# EMoC_Page1.net
KiCad netlist of a schematic drawn in Altium Designer
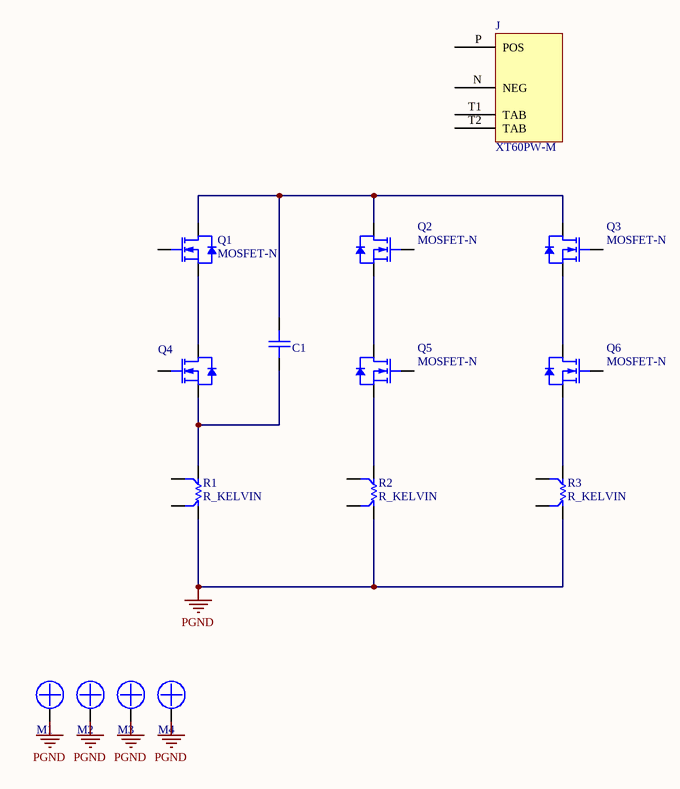
[diagram p0: EMoC_Page1.SchDoc]

(export (version "E")
  (design (tool "Eeschema 10.0.6"))
  (components
    (comp (ref "C1") (value "~") (footprint "C0603N") (libsource (lib "libysk") (part "C")))
    (comp (ref "J")
      (value "XT60PW-M")
      (footprint "XT60PW-M")
      (description "XT60, Male, THT, R/A")
      (libsource (lib "libysk") (part "XT60PW-M"))
    )
    (comp (ref "M1")
      (value "Mounting_Screw")
      (footprint "MOUNT_HOLE_3.2")
      (libsource (lib "libysk") (part "Mounting_Screw"))
    )
    (comp (ref "M2")
      (value "Mounting_Screw")
      (footprint "MOUNT_HOLE_3.2")
      (libsource (lib "libysk") (part "Mounting_Screw"))
    )
    (comp (ref "M3")
      (value "Mounting_Screw")
      (footprint "MOUNT_HOLE_3.2")
      (libsource (lib "libysk") (part "Mounting_Screw"))
    )
    (comp (ref "M4")
      (value "Mounting_Screw")
      (footprint "MOUNT_HOLE_3.2")
      (libsource (lib "libysk") (part "Mounting_Screw"))
    )
    (comp (ref "Q1")
      (value "MOSFET-N")
      (footprint "DFN-5 (SO-8FL)")
      (libsource (lib "libysk") (part "MOSFET-N"))
    )
    (comp (ref "Q2")
      (value "MOSFET-N")
      (footprint "DFN-5 (SO-8FL)")
      (libsource (lib "libysk") (part "MOSFET-N"))
    )
    (comp (ref "Q3")
      (value "MOSFET-N")
      (footprint "DFN-5 (SO-8FL)")
      (libsource (lib "libysk") (part "MOSFET-N"))
    )
    (comp (ref "Q4")
      (value "MOSFET-N")
      (footprint "DFN-5 (SO-8FL)")
      (libsource (lib "libysk") (part "MOSFET-N"))
    )
    (comp (ref "Q5")
      (value "MOSFET-N")
      (footprint "DFN-5 (SO-8FL)")
      (libsource (lib "libysk") (part "MOSFET-N"))
    )
    (comp (ref "Q6")
      (value "MOSFET-N")
      (footprint "DFN-5 (SO-8FL)")
      (libsource (lib "libysk") (part "MOSFET-N"))
    )
    (comp (ref "R1")
      (value "R_KELVIN")
      (footprint "CSS2H-2512N_KELVIN")
      (libsource (lib "libysk") (part "R_KELVIN"))
    )
    (comp (ref "R2")
      (value "R_KELVIN")
      (footprint "CSS2H-2512N_KELVIN")
      (libsource (lib "libysk") (part "R_KELVIN"))
    )
    (comp (ref "R3")
      (value "R_KELVIN")
      (footprint "CSS2H-2512N_KELVIN")
      (libsource (lib "libysk") (part "R_KELVIN"))
    )
  )
  (nets
    (net (code "1") (name "Net-(C1-Pad1)") (class "Default")
      (node (ref "C1") (pin "1") (pinfunction "1_1") (pintype "passive"))
      (node (ref "Q4") (pin "S") (pinfunction "S_S") (pintype "passive"))
      (node (ref "R1") (pin "2") (pinfunction "2_2") (pintype "passive"))
    )
    (net (code "2") (name "Net-(C1-Pad2)") (class "Default")
      (node (ref "C1") (pin "2") (pinfunction "2_2") (pintype "passive"))
      (node (ref "Q1") (pin "D") (pinfunction "D_D") (pintype "passive"))
      (node (ref "Q2") (pin "D") (pinfunction "D_D") (pintype "passive"))
      (node (ref "Q3") (pin "D") (pinfunction "D_D") (pintype "passive"))
    )
    (net (code "3") (name "Net-(Q1-PadS)") (class "Default")
      (node (ref "Q1") (pin "S") (pinfunction "S_S") (pintype "passive"))
      (node (ref "Q4") (pin "D") (pinfunction "D_D") (pintype "passive"))
    )
    (net (code "4") (name "Net-(Q2-PadS)") (class "Default")
      (node (ref "Q2") (pin "S") (pinfunction "S_S") (pintype "passive"))
      (node (ref "Q5") (pin "D") (pinfunction "D_D") (pintype "passive"))
    )
    (net (code "5") (name "Net-(Q3-PadS)") (class "Default")
      (node (ref "Q3") (pin "S") (pinfunction "S_S") (pintype "passive"))
      (node (ref "Q6") (pin "D") (pinfunction "D_D") (pintype "passive"))
    )
    (net (code "6") (name "Net-(Q5-PadS)") (class "Default")
      (node (ref "Q5") (pin "S") (pinfunction "S_S") (pintype "passive"))
      (node (ref "R2") (pin "2") (pinfunction "2_2") (pintype "passive"))
    )
    (net (code "7") (name "Net-(Q6-PadS)") (class "Default")
      (node (ref "Q6") (pin "S") (pinfunction "S_S") (pintype "passive"))
      (node (ref "R3") (pin "2") (pinfunction "2_2") (pintype "passive"))
    )
    (net (code "8") (name "PGND") (class "Default")
      (node (ref "M1") (pin "1") (pinfunction "1_1") (pintype "passive"))
      (node (ref "M2") (pin "1") (pinfunction "1_1") (pintype "passive"))
      (node (ref "M3") (pin "1") (pinfunction "1_1") (pintype "passive"))
      (node (ref "M4") (pin "1") (pinfunction "1_1") (pintype "passive"))
      (node (ref "R1") (pin "1") (pinfunction "1_1") (pintype "passive"))
      (node (ref "R2") (pin "1") (pinfunction "1_1") (pintype "passive"))
      (node (ref "R3") (pin "1") (pinfunction "1_1") (pintype "passive"))
    )
    (net (code "9") (name "unconnected-(J-NEG-PadN)") (class "Default")
      (node (ref "J") (pin "N") (pinfunction "NEG_N") (pintype "passive"))
    )
    (net (code "10") (name "unconnected-(J-POS-PadP)") (class "Default")
      (node (ref "J") (pin "P") (pinfunction "POS_P") (pintype "passive"))
    )
    (net (code "11") (name "unconnected-(J-TAB-PadT1)") (class "Default")
      (node (ref "J") (pin "T1") (pinfunction "TAB_T1") (pintype "passive"))
    )
    (net (code "12") (name "unconnected-(J-TAB-PadT2)") (class "Default")
      (node (ref "J") (pin "T2") (pinfunction "TAB_T2") (pintype "passive"))
    )
    (net (code "13") (name "unconnected-(Q1-PadG)") (class "Default")
      (node (ref "Q1") (pin "G") (pinfunction "G_G") (pintype "passive"))
    )
    (net (code "14") (name "unconnected-(Q2-PadG)") (class "Default")
      (node (ref "Q2") (pin "G") (pinfunction "G_G") (pintype "passive"))
    )
    (net (code "15") (name "unconnected-(Q3-PadG)") (class "Default")
      (node (ref "Q3") (pin "G") (pinfunction "G_G") (pintype "passive"))
    )
    (net (code "16") (name "unconnected-(Q4-PadG)") (class "Default")
      (node (ref "Q4") (pin "G") (pinfunction "G_G") (pintype "passive"))
    )
    (net (code "17") (name "unconnected-(Q5-PadG)") (class "Default")
      (node (ref "Q5") (pin "G") (pinfunction "G_G") (pintype "passive"))
    )
    (net (code "18") (name "unconnected-(Q6-PadG)") (class "Default")
      (node (ref "Q6") (pin "G") (pinfunction "G_G") (pintype "passive"))
    )
    (net (code "19") (name "unconnected-(R1-Pad3)") (class "Default")
      (node (ref "R1") (pin "3") (pinfunction "3_3") (pintype "passive"))
    )
    (net (code "20") (name "unconnected-(R1-Pad4)") (class "Default")
      (node (ref "R1") (pin "4") (pinfunction "4_4") (pintype "passive"))
    )
    (net (code "21") (name "unconnected-(R2-Pad3)") (class "Default")
      (node (ref "R2") (pin "3") (pinfunction "3_3") (pintype "passive"))
    )
    (net (code "22") (name "unconnected-(R2-Pad4)") (class "Default")
      (node (ref "R2") (pin "4") (pinfunction "4_4") (pintype "passive"))
    )
    (net (code "23") (name "unconnected-(R3-Pad3)") (class "Default")
      (node (ref "R3") (pin "3") (pinfunction "3_3") (pintype "passive"))
    )
    (net (code "24") (name "unconnected-(R3-Pad4)") (class "Default")
      (node (ref "R3") (pin "4") (pinfunction "4_4") (pintype "passive"))
    )
  )
)
